# PCA_0008_USB_REV_B.net
KiCad netlist of a schematic drawn in Altium Designer
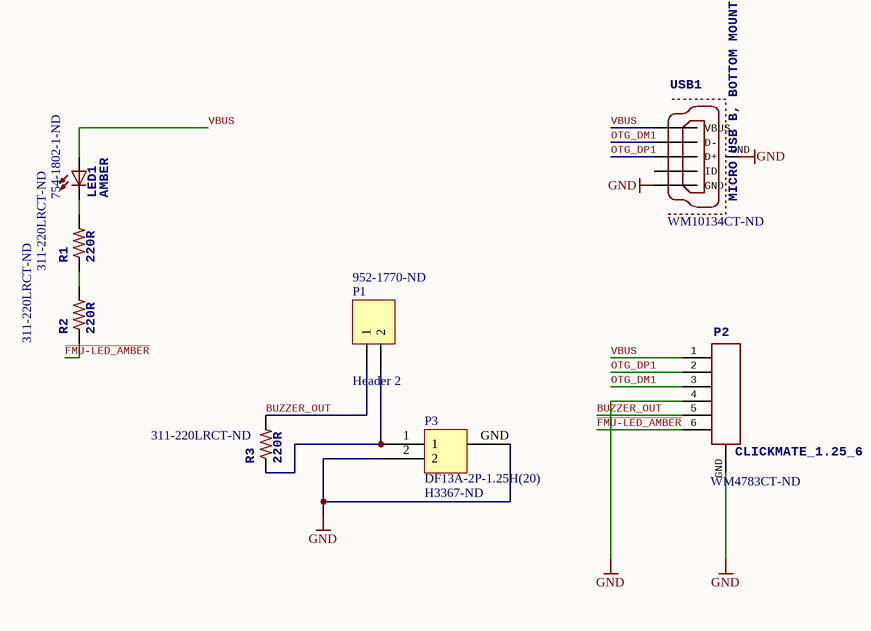
[diagram p0: PCA_0008_USB_REV_B.SchDoc]

(export (version "E")
  (design (tool "Eeschema 10.0.6"))
  (components
    (comp (ref "LED1")
      (value "AMBER")
      (footprint "0603-LED")
      (fields
        (field (name "PARTNO") "APTD1608SECK")
        (field (name "SUPPLIER PART NUMBER 1") "754-1802-1-ND")
        (field (name "3DR_PARTNO") "ECM0515")
      )
      (libsource (lib "pixhawk2") (part "LED0603"))
    )
    (comp (ref "P1")
      (value "Header 2")
      (footprint "HDR1X2")
      (description "Header, 2-Pin")
      (fields
        (field (name "SUPPLIER PART NUMBER 1") "952-1770-ND")
        (field (name "PUBLISHER") "Altium Limited")
      )
      (libsource (lib "Miscellaneous Connectors") (part "Header 2"))
    )
    (comp (ref "P2")
      (value "CLICKMATE_1.25_6")
      (footprint "CLICKMATE_V6")
      (fields (field (name "SUPPLIER PART NUMBER 1") "WM4783CT-ND") (field (name "3DR_PARTNO") "ECM0520"))
      (libsource (lib "pixhawk2") (part "CLICKMATE_1.25_6"))
    )
    (comp (ref "P3")
      (value "DF13A-2P-1.25H(20)")
      (footprint "DF13A-2P-1.25H(20)")
      (fields (field (name "SUPPLIER PART NUMBER 1") "H3367-ND"))
      (libsource (lib "pixhawk2") (part "DF13A-2P-1.25H(20)"))
    )
    (comp (ref "R1")
      (value "220R")
      (footprint "0402-RES")
      (fields
        (field (name "PARTNO") "RC0402FR-07220RL")
        (field (name "SUPPLIER PART NUMBER 1") "311-220LRCT-ND")
        (field (name "3DR_PARTNO") "ECM0821")
      )
      (libsource (lib "pixhawk2") (part "RESISTOR0402-RES"))
    )
    (comp (ref "R2")
      (value "220R")
      (footprint "0402-RES")
      (fields
        (field (name "PARTNO") "RC0402FR-07220RL")
        (field (name "SUPPLIER PART NUMBER 1") "311-220LRCT-ND")
        (field (name "3DR_PARTNO") "ECM0821")
      )
      (libsource (lib "pixhawk2") (part "RESISTOR0402-RES"))
    )
    (comp (ref "R3")
      (value "220R")
      (footprint "0402-RES")
      (fields
        (field (name "PARTNO") "RC0402FR-07220RL")
        (field (name "SUPPLIER PART NUMBER 1") "311-220LRCT-ND")
        (field (name "3DR_PARTNO") "ECM0821")
      )
      (libsource (lib "pixhawk2") (part "RESISTOR0402-RES"))
    )
    (comp (ref "USB1")
      (value "MICRO USB B, BOTTOM MOUNT")
      (footprint "USB_10513300111051330011_Vert")
      (fields (field (name "SUPPLIER PART NUMBER 1") "WM10134CT-ND"))
      (libsource (lib "pixhawk2") (part "MOLEX-1051330011-VERT"))
    )
  )
  (nets
    (net (code "1") (name "/BUZZER_OUT") (class "Default")
      (node (ref "P1") (pin "1") (pinfunction "1_1") (pintype "passive"))
      (node (ref "P2") (pin "5") (pinfunction "5_5") (pintype "passive"))
      (node (ref "R3") (pin "P$2") (pinfunction "2_P$2") (pintype "passive"))
    )
    (net (code "2") (name "/OTG_DM1") (class "Default")
      (node (ref "P2") (pin "3") (pinfunction "3_3") (pintype "passive"))
      (node (ref "USB1") (pin "2") (pinfunction "D-_2") (pintype "passive"))
    )
    (net (code "3") (name "/OTG_DP1") (class "Default")
      (node (ref "P2") (pin "2") (pinfunction "2_2") (pintype "passive"))
      (node (ref "USB1") (pin "3") (pinfunction "D+_3") (pintype "passive"))
    )
    (net (code "4") (name "/VBUS") (class "Default")
      (node (ref "LED1") (pin "A") (pinfunction "A_A") (pintype "passive"))
      (node (ref "P2") (pin "1") (pinfunction "1_1") (pintype "passive"))
      (node (ref "USB1") (pin "1") (pinfunction "VBUS_1") (pintype "open_emitter"))
    )
    (net (code "5") (name "/~{FMU-LED_AMBER}") (class "Default")
      (node (ref "P2") (pin "6") (pinfunction "6_6") (pintype "passive"))
      (node (ref "R2") (pin "P$1") (pinfunction "1_P$1") (pintype "passive"))
    )
    (net (code "6") (name "GND") (class "Default")
      (node (ref "P2") (pin "4") (pinfunction "4_4") (pintype "passive"))
      (node (ref "P2") (pin "GND") (pinfunction "GND_GND") (pintype "passive"))
      (node (ref "P3") (pin "2") (pinfunction "2_2") (pintype "passive"))
      (node (ref "P3") (pin "GND") (pinfunction "3_GND") (pintype "passive"))
      (node (ref "USB1") (pin "5") (pinfunction "GND_5") (pintype "open_emitter"))
      (node (ref "USB1") (pin "GND") (pinfunction "GND_GND") (pintype "passive"))
    )
    (net (code "7") (name "Net-(R1-1)") (class "Default")
      (node (ref "R1") (pin "P$1") (pinfunction "1_P$1") (pintype "passive"))
      (node (ref "R2") (pin "P$2") (pinfunction "2_P$2") (pintype "passive"))
    )
    (net (code "8") (name "Net-(R1-2)") (class "Default")
      (node (ref "LED1") (pin "C") (pinfunction "C_C") (pintype "passive"))
      (node (ref "R1") (pin "P$2") (pinfunction "2_P$2") (pintype "passive"))
    )
    (net (code "9") (name "Net-(R3-1)") (class "Default")
      (node (ref "P1") (pin "2") (pinfunction "2_2") (pintype "passive"))
      (node (ref "P3") (pin "1") (pinfunction "1_1") (pintype "passive"))
      (node (ref "R3") (pin "P$1") (pinfunction "1_P$1") (pintype "passive"))
    )
    (net (code "10") (name "unconnected-(USB1-ID-Pad4)") (class "Default")
      (node (ref "USB1") (pin "4") (pinfunction "ID_4") (pintype "passive"))
    )
  )
)
